# Root_page.net
KiCad netlist of a schematic drawn in Altium Designer
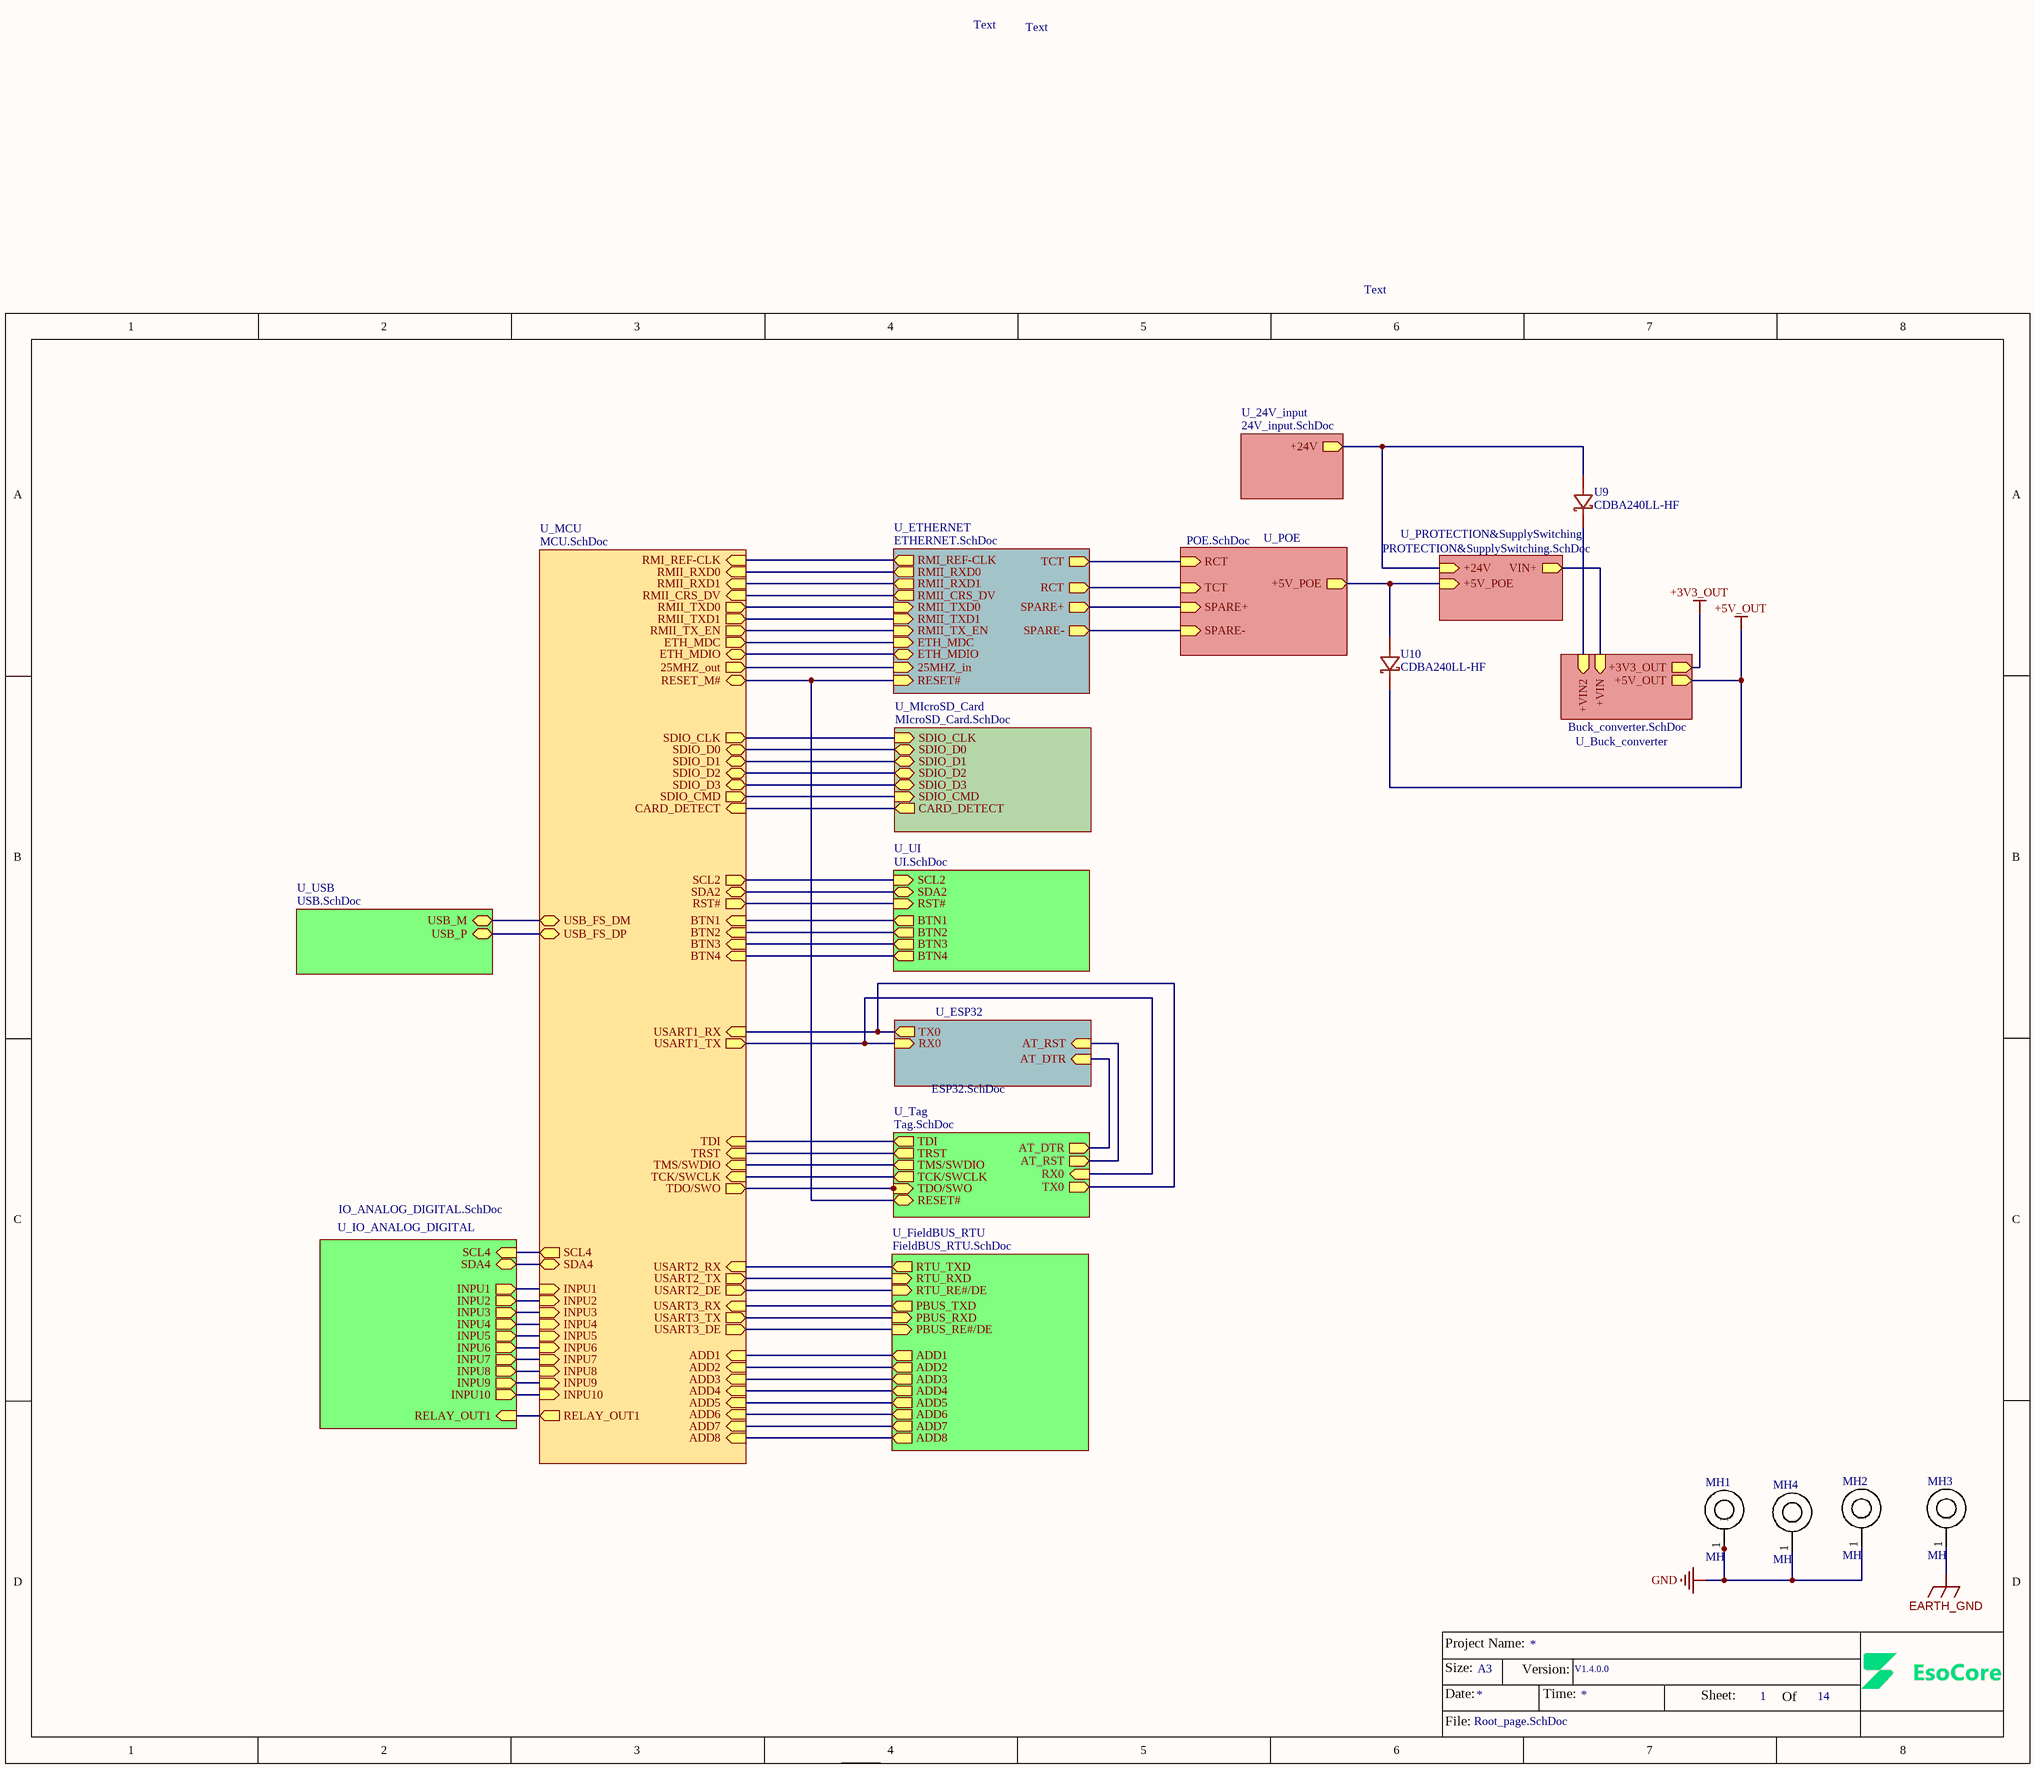
[diagram p0: Root_page.SchDoc]

(export (version "E")
  (design (tool "Eeschema 10.0.6"))
  (components
    (comp (ref "MH1")
      (value "MH")
      (footprint "MountingHole_3.2mm_M3_Pad_Via")
      (libsource (lib "Schlib1") (part "MH"))
    )
    (comp (ref "MH2")
      (value "MH")
      (footprint "MountingHole_3.2mm_M3_Pad_Via")
      (libsource (lib "Schlib1") (part "MH"))
    )
    (comp (ref "MH3")
      (value "MH")
      (footprint "MountingHole_3.2mm_M3_Pad_Via")
      (libsource (lib "Schlib1") (part "MH"))
    )
    (comp (ref "MH4")
      (value "MH")
      (footprint "MountingHole_3.2mm_M3_Pad_Via")
      (libsource (lib "Schlib1") (part "MH"))
    )
    (comp (ref "U9")
      (value "CDBA240LL-HF")
      (footprint "SMA_L4.4-W2.5-LS5.2-R-RD")
      (fields (field (name "MANUFACTURER") "Comchip(典琦)"))
      (libsource (lib "altium-import") (part "root_1_CDBA240LL-HF_"))
    )
    (comp (ref "U10")
      (value "CDBA240LL-HF")
      (footprint "SMA_L4.4-W2.5-LS5.2-R-RD")
      (fields (field (name "MANUFACTURER") "Comchip(典琦)"))
      (libsource (lib "altium-import") (part "root_1_CDBA240LL-HF_"))
    )
  )
  (nets
    (net (code "2") (name "+5V_OUT") (class "Default")
      (node (ref "U10") (pin "2") (pinfunction "K_2") (pintype "passive"))
    )
    (net (code "3") (name "/+5V_POE") (class "Default")
      (node (ref "U10") (pin "1") (pinfunction "A_1") (pintype "passive"))
    )
    (net (code "4") (name "/+24V") (class "Default")
      (node (ref "U9") (pin "1") (pinfunction "A_1") (pintype "passive"))
    )
    (net (code "5") (name "/+VIN2") (class "Default")
      (node (ref "U9") (pin "2") (pinfunction "K_2") (pintype "passive"))
    )
    (net (code "74") (name "EARTH_GND") (class "Default")
      (node (ref "MH3") (pin "1") (pinfunction "1_1") (pintype "passive"))
    )
    (net (code "75") (name "GND") (class "Default")
      (node (ref "MH1") (pin "1") (pinfunction "1_1") (pintype "passive"))
      (node (ref "MH2") (pin "1") (pinfunction "1_1") (pintype "passive"))
      (node (ref "MH4") (pin "1") (pinfunction "1_1") (pintype "passive"))
    )
  )
)
